# RX-FM-Radio-Simple.net
KiCad netlist of a schematic drawn in EAGLE
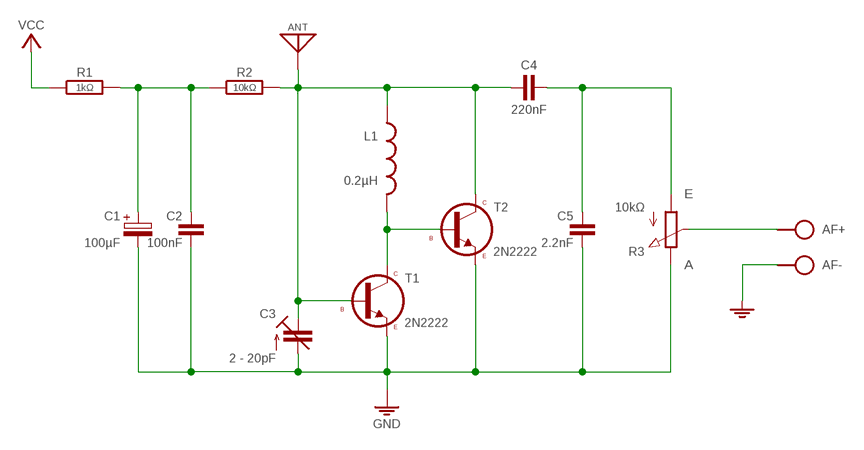
[diagram p0: schematic, sheet 1]

(export (version "E")
  (design (tool "Eeschema 10.0.6"))
  (components
    (comp (ref "AF")
      (value "SPAD+-+-")
      (footprint "eagle-import:SPAD+-")
      (libsource (lib "eagle-import") (part "SPAD+-+-"))
    )
    (comp (ref "ANT")
      (value "ANT")
      (footprint "eagle-import:SPAD")
      (libsource (lib "eagle-import") (part "ANT"))
    )
    (comp (ref "BAT")
      (value "VCC_GNDL")
      (footprint "eagle-import:SPAD-+")
      (libsource (lib "eagle-import") (part "VCC_GNDL"))
    )
    (comp (ref "C1")
      (value "100µF")
      (footprint "eagle-import:E2,5-5_V")
      (libsource (lib "eagle-import") (part "CPOLE2,5-5/V"))
    )
    (comp (ref "C2")
      (value "100nF")
      (footprint "eagle-import:C050-020X036_V")
      (libsource (lib "eagle-import") (part "C050-020X036/V"))
    )
    (comp (ref "C3")
      (value "2 - 20pF")
      (footprint "eagle-import:TRIM-2222-808")
      (libsource (lib "eagle-import") (part "C-TR-PH201272222-808-2PIND"))
    )
    (comp (ref "C4")
      (value "220nF")
      (footprint "eagle-import:C050-020X044")
      (libsource (lib "eagle-import") (part "C-H050-020X044"))
    )
    (comp (ref "C5")
      (value "2.2nF")
      (footprint "eagle-import:C050-020X036_V")
      (libsource (lib "eagle-import") (part "C050-020X036/V"))
    )
    (comp (ref "L1")
      (value "0.2µH")
      (footprint "eagle-import:L-10_10X")
      (libsource (lib "eagle-import") (part "L10/10X"))
    )
    (comp (ref "R1")
      (value "1kΩ")
      (footprint "eagle-import:0204_10")
      (libsource (lib "eagle-import") (part "R-H0204/10"))
    )
    (comp (ref "R2")
      (value "10kΩ")
      (footprint "eagle-import:0204_10")
      (libsource (lib "eagle-import") (part "R-H0204/10"))
    )
    (comp (ref "R3")
      (value "10kΩ")
      (footprint "eagle-import:POT")
      (libsource (lib "eagle-import") (part "POT"))
    )
    (comp (ref "T1")
      (value "2N2222")
      (footprint "eagle-import:TO92")
      (libsource (lib "eagle-import") (part "2N2222"))
    )
    (comp (ref "T2")
      (value "2N2222")
      (footprint "eagle-import:TO92")
      (libsource (lib "eagle-import") (part "2N2222"))
    )
  )
  (nets
    (net (code "1") (name "GND") (class "Default")
      (node (ref "AF") (pin "1") (pinfunction "P$1_1") (pintype "passive"))
      (node (ref "BAT") (pin "1") (pinfunction "GND_1") (pintype "power_in"))
      (node (ref "C1") (pin "-") (pinfunction "-_-") (pintype "passive"))
      (node (ref "C2") (pin "2") (pinfunction "2_2") (pintype "passive"))
      (node (ref "C3") (pin "2") (pinfunction "A_2") (pintype "passive"))
      (node (ref "C5") (pin "2") (pinfunction "2_2") (pintype "passive"))
      (node (ref "R3") (pin "E") (pinfunction "E_E") (pintype "passive"))
      (node (ref "T1") (pin "1") (pinfunction "E_1") (pintype "passive"))
      (node (ref "T2") (pin "1") (pinfunction "E_1") (pintype "passive"))
    )
    (net (code "2") (name "Net-(AFA-P$1)") (class "Default")
      (node (ref "AF") (pin "2") (pinfunction "P$1_2") (pintype "passive"))
      (node (ref "R3") (pin "S") (pinfunction "S_S") (pintype "passive"))
    )
    (net (code "3") (name "Net-(BATA-VCC)") (class "Default")
      (node (ref "BAT") (pin "2") (pinfunction "VCC_2") (pintype "power_in"))
      (node (ref "R1") (pin "1") (pinfunction "1_1") (pintype "passive"))
    )
    (net (code "4") (name "Net-(C1-Pad+)") (class "Default")
      (node (ref "C1") (pin "+") (pinfunction "+_+") (pintype "passive"))
      (node (ref "C2") (pin "1") (pinfunction "1_1") (pintype "passive"))
      (node (ref "R1") (pin "2") (pinfunction "2_2") (pintype "passive"))
      (node (ref "R2") (pin "1") (pinfunction "1_1") (pintype "passive"))
    )
    (net (code "5") (name "Net-(C3-E)") (class "Default")
      (node (ref "ANT") (pin "1") (pinfunction "1_1") (pintype "output"))
      (node (ref "C3") (pin "3") (pinfunction "E_3") (pintype "passive"))
      (node (ref "C4") (pin "1") (pinfunction "1_1") (pintype "passive"))
      (node (ref "L1") (pin "P$1") (pinfunction "1_P$1") (pintype "passive"))
      (node (ref "R2") (pin "2") (pinfunction "2_2") (pintype "passive"))
      (node (ref "T1") (pin "2") (pinfunction "B_2") (pintype "passive"))
      (node (ref "T2") (pin "3") (pinfunction "C_3") (pintype "passive"))
    )
    (net (code "6") (name "Net-(C4-Pad2)") (class "Default")
      (node (ref "C4") (pin "2") (pinfunction "2_2") (pintype "passive"))
      (node (ref "C5") (pin "1") (pinfunction "1_1") (pintype "passive"))
      (node (ref "R3") (pin "A") (pinfunction "A_A") (pintype "passive"))
    )
    (net (code "7") (name "Net-(L1-2)") (class "Default")
      (node (ref "L1") (pin "P$2") (pinfunction "2_P$2") (pintype "passive"))
      (node (ref "T1") (pin "3") (pinfunction "C_3") (pintype "passive"))
      (node (ref "T2") (pin "2") (pinfunction "B_2") (pintype "passive"))
    )
  )
)
